# USB_to_UART_controller.net
KiCad netlist of a schematic drawn in Altium Designer
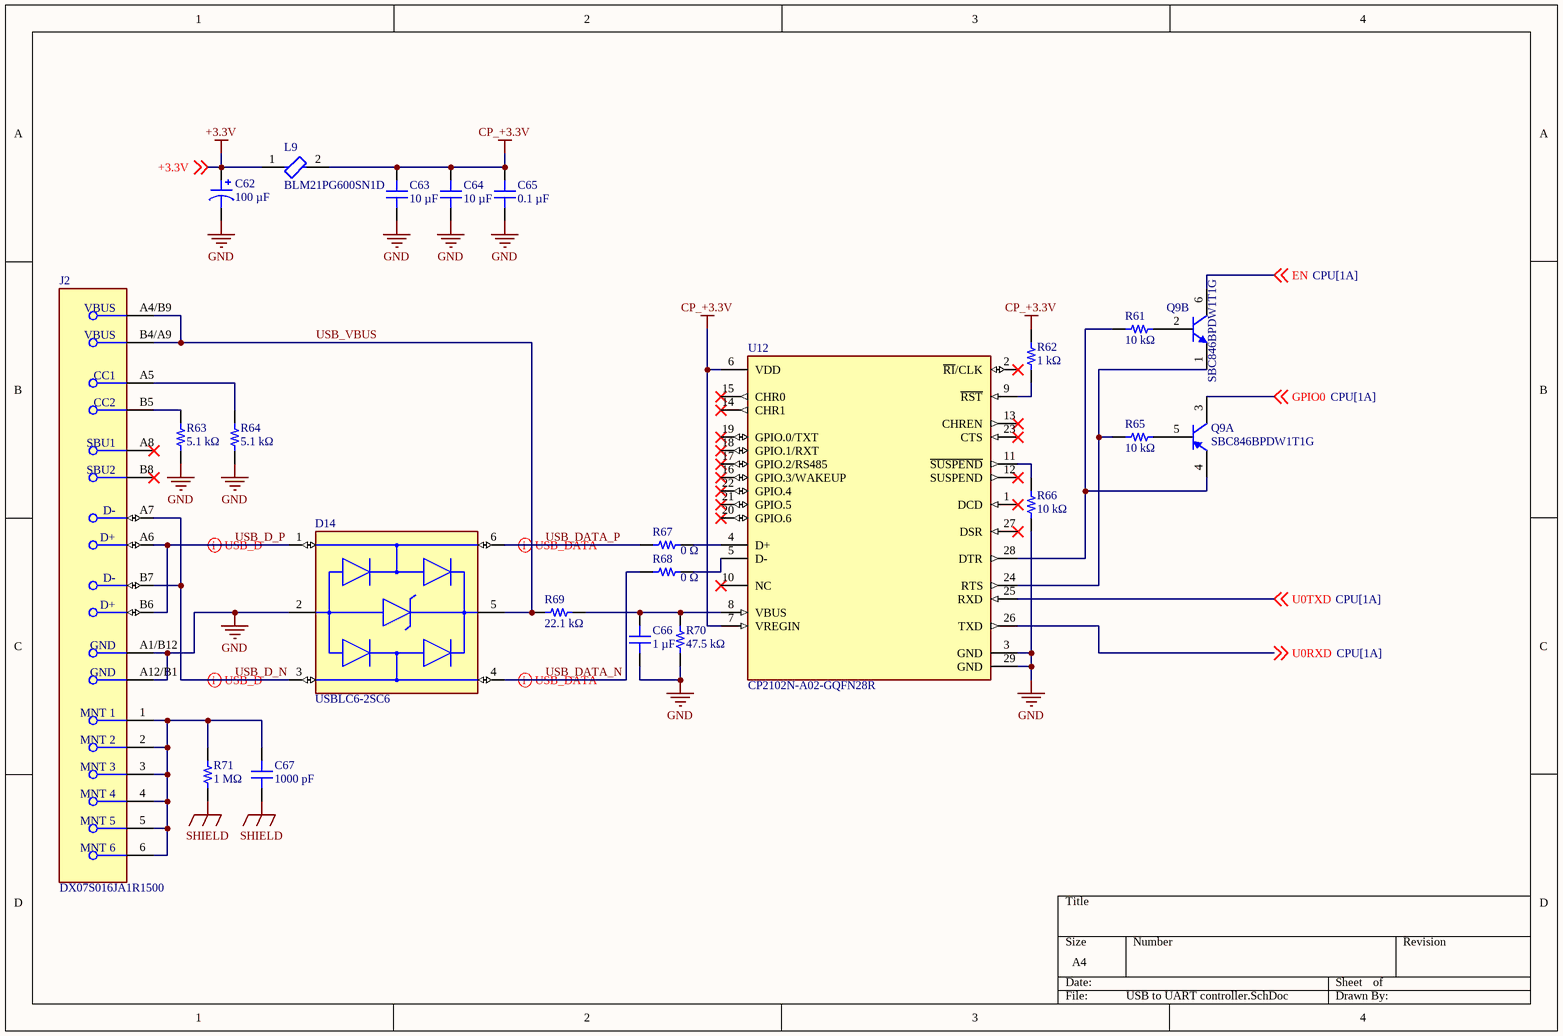
[diagram p0: USB to UART controller.SchDoc]

(export (version "E")
  (design (tool "Eeschema 10.0.6"))
  (components
    (comp (ref "C62")
      (value "100 µF")
      (footprint "CAP POL 1411_3528")
      (description "CAP TANT 100UF 20% 6.3V 1411")
      (fields (field (name "PART NUMBER") "T494B107M006AT") (field (name "MANUFACTURER") "KEMET"))
      (libsource (lib "Celestial Altium Library - altium_library") (part "Polarised Capacitor"))
    )
    (comp (ref "C63")
      (value "10 µF")
      (footprint "CAP 0805_2012")
      (description "CAP CER 10UF 6.3V X7R 0805")
      (fields
        (field (name "PART NUMBER") "CGA4J1X7R0J106K125AC")
        (field (name "CAPACITANCE") "10 µF")
        (field (name "MANUFACTURER") "TDK Corporation")
      )
      (libsource (lib "Celestial Altium Library - altium_library") (part "Capacitor"))
    )
    (comp (ref "C64")
      (value "10 µF")
      (footprint "CAP 0805_2012")
      (description "CAP CER 10UF 6.3V X7R 0805")
      (fields
        (field (name "PART NUMBER") "CGA4J1X7R0J106K125AC")
        (field (name "CAPACITANCE") "10 µF")
        (field (name "MANUFACTURER") "TDK Corporation")
      )
      (libsource (lib "Celestial Altium Library - altium_library") (part "Capacitor"))
    )
    (comp (ref "C65")
      (value "0.1 µF")
      (footprint "CAP 0603_1608")
      (description "CAP CER 0.1UF 50V X7R 0603")
      (fields
        (field (name "PART NUMBER") "C1608X7R1H104K080AE")
        (field (name "CAPACITANCE") "0.1 µF")
        (field (name "MANUFACTURER") "TDK Corporation")
      )
      (libsource (lib "Celestial Altium Library - altium_library") (part "Capacitor"))
    )
    (comp (ref "C66")
      (value "1 µF")
      (footprint "CAP 0805_2012")
      (description "CAP CER 1UF 25V X7R 0805")
      (fields
        (field (name "PART NUMBER") "C2012X7R1E105K125AB")
        (field (name "CAPACITANCE") "1 µF")
        (field (name "MANUFACTURER") "TDK Corporation")
      )
      (libsource (lib "Celestial Altium Library - altium_library") (part "Capacitor"))
    )
    (comp (ref "C67")
      (value "1000 pF")
      (footprint "CAP 1210_3225 - 1MM")
      (description "CAP CER 1000PF 2KV C0G/NP0 1210")
      (fields (field (name "PART NUMBER") "KGM32LCG3D102JU") (field (name "MANUFACTURER") "KYOCERA AVX"))
      (libsource (lib "Celestial Altium Library - altium_library") (part "Capacitor"))
    )
    (comp (ref "D14")
      (value "USBLC6-2SC6")
      (footprint "FP-SOT-666-MFG")
      (description "TVS DIODE 5.25V 17V SOT666")
      (fields (field (name "MANUFACTURER") "STMicroelectronics"))
      (libsource (lib "Altium Content Vault") (part "c871e55f7e3243d341edbd671b98d92"))
    )
    (comp (ref "J2")
      (value "DX07S016JA1R1500")
      (footprint "FP-DX07S016JA1R1500-MFG")
      (description "CONN RCP USB2.0 TYP C 24P SMD RA")
      (libsource (lib "Altium Content Vault") (part "7f3e9989102a0f22bff9cb010881d34"))
    )
    (comp (ref "L9")
      (value "BLM21PG600SN1D")
      (footprint "FP-BLM21-0_2-t0_85-e0_5-d-IPC_A")
      (description "Chip Ferrite Bead, 0805, 60Ω @ 100MHz, 0.02Ω, 25%, 3.5A")
      (fields (field (name "TOLERANCE") "25%"))
      (libsource (lib "Altium Content Vault") (part "5f30dd21d616792df468990f7003faa"))
    )
    (comp (ref "Q9")
      (value "SBC846BPDW1T1G")
      (footprint "ONSC-SOT-363-6-419B-02_V")
      (description "Dual General Purpose Transistors, NPN / PNP (Complementary), 6-Pin SOT-363, Pb-Free, Tape and Reel")
      (fields (field (name "MANUFACTURER") "On Semiconductor"))
      (libsource (lib "Altium Content Vault") (part "ONSC-NPN_PNP-6"))
    )
    (comp (ref "R61")
      (value "10 kΩ")
      (footprint "RES 0603_1608")
      (description "RES SMD 10K OHM 1% 1/10W 0603")
      (fields (field (name "PART NUMBER") "CRCW060310K0FKEA") (field (name "MANUFACTURER") "Vishay Dale"))
      (libsource (lib "Celestial Altium Library - altium_library") (part "Resistor"))
    )
    (comp (ref "R62")
      (value "1 kΩ")
      (footprint "RES 0603_1608")
      (description "RES SMD 1K OHM 1% 1/10W 0603")
      (fields (field (name "PART NUMBER") "CRCW06031K00FKEA") (field (name "MANUFACTURER") "Vishay Dale"))
      (libsource (lib "Celestial Altium Library - altium_library") (part "Resistor"))
    )
    (comp (ref "R63")
      (value "5.1 kΩ")
      (footprint "RES 0603_1608")
      (description "RES SMD 5.1K OHM 1% 1/10W 0603")
      (fields (field (name "PART NUMBER") "CRCW06035K10FKEA") (field (name "MANUFACTURER") "Vishay Dale"))
      (libsource (lib "Celestial Altium Library - altium_library") (part "Resistor"))
    )
    (comp (ref "R64")
      (value "5.1 kΩ")
      (footprint "RES 0603_1608")
      (description "RES SMD 5.1K OHM 1% 1/10W 0603")
      (fields (field (name "PART NUMBER") "CRCW06035K10FKEA") (field (name "MANUFACTURER") "Vishay Dale"))
      (libsource (lib "Celestial Altium Library - altium_library") (part "Resistor"))
    )
    (comp (ref "R65")
      (value "10 kΩ")
      (footprint "RES 0603_1608")
      (description "RES SMD 10K OHM 1% 1/10W 0603")
      (fields (field (name "PART NUMBER") "CRCW060310K0FKEA") (field (name "MANUFACTURER") "Vishay Dale"))
      (libsource (lib "Celestial Altium Library - altium_library") (part "Resistor"))
    )
    (comp (ref "R66")
      (value "10 kΩ")
      (footprint "RES 0603_1608")
      (description "RES SMD 10K OHM 1% 1/10W 0603")
      (fields (field (name "PART NUMBER") "CRCW060310K0FKEA") (field (name "MANUFACTURER") "Vishay Dale"))
      (libsource (lib "Celestial Altium Library - altium_library") (part "Resistor"))
    )
    (comp (ref "R67")
      (value "0 Ω")
      (footprint "RES 0603_1608")
      (description "RES SMD 0 OHM JUMPER 1/10W 0603")
      (fields
        (field (name "PART NUMBER") "ERJ-3GEY0R00V")
        (field (name "MANUFACTURER") "Panasonic Electronic Components")
      )
      (libsource (lib "Celestial Altium Library - altium_library") (part "Resistor"))
    )
    (comp (ref "R68")
      (value "0 Ω")
      (footprint "RES 0603_1608")
      (description "RES SMD 0 OHM JUMPER 1/10W 0603")
      (fields
        (field (name "PART NUMBER") "ERJ-3GEY0R00V")
        (field (name "MANUFACTURER") "Panasonic Electronic Components")
      )
      (libsource (lib "Celestial Altium Library - altium_library") (part "Resistor"))
    )
    (comp (ref "R69")
      (value "22.1 kΩ")
      (footprint "RES 0603_1608")
      (description "RES SMD 22.1K OHM 1% 1/10W 0603")
      (fields (field (name "PART NUMBER") "CRCW060322K1FKEA") (field (name "MANUFACTURER") "Vishay Dale"))
      (libsource (lib "Celestial Altium Library - altium_library") (part "Resistor"))
    )
    (comp (ref "R70")
      (value "47.5 kΩ")
      (footprint "RES 0603_1608")
      (description "RES SMD 47.5K OHM 1% 1/10W 0603")
      (fields (field (name "PART NUMBER") "CRCW060347K5FKEA") (field (name "MANUFACTURER") "Vishay Dale"))
      (libsource (lib "Celestial Altium Library - altium_library") (part "Resistor"))
    )
    (comp (ref "R71")
      (value "1 MΩ")
      (footprint "RES 0805_2012")
      (description "RES SMD 1M OHM 1% 1/2W 0805")
      (fields (field (name "PART NUMBER") "RCS08051M00FKEA") (field (name "MANUFACTURER") "Vishay Dale"))
      (libsource (lib "Celestial Altium Library - altium_library") (part "Resistor"))
    )
    (comp (ref "U12")
      (value "CP2102N-A02-GQFN28R")
      (footprint "FP-CP2102N-A02-GQFN28R-MFG")
      (description "IC USB TO UART BRIDGE QFN28")
      (libsource (lib "Altium Content Vault") (part "670edaef084fb69d2a747396d70a05e"))
    )
  )
  (nets
    (net (code "1") (name "+3.3V") (class "Default")
      (node (ref "C62") (pin "1") (pinfunction "1_1") (pintype "passive"))
      (node (ref "L9") (pin "1") (pinfunction "1_1") (pintype "passive"))
    )
    (net (code "2") (name "/USB_DATA_N") (class "Default")
      (node (ref "D14") (pin "4") (pinfunction "I/O2_4") (pintype "bidirectional"))
      (node (ref "R68") (pin "1") (pinfunction "1_1") (pintype "passive"))
    )
    (net (code "3") (name "/USB_DATA_P") (class "Default")
      (node (ref "D14") (pin "6") (pinfunction "I/O1_6") (pintype "bidirectional"))
      (node (ref "R67") (pin "1") (pinfunction "1_1") (pintype "passive"))
    )
    (net (code "4") (name "/USB_D_N") (class "Default")
      (node (ref "D14") (pin "3") (pinfunction "I/O2_3") (pintype "bidirectional"))
      (node (ref "J2") (pin "A7") (pinfunction "D-_A7") (pintype "bidirectional"))
      (node (ref "J2") (pin "B7") (pinfunction "D-_B7") (pintype "bidirectional"))
    )
    (net (code "5") (name "/USB_D_P") (class "Default")
      (node (ref "D14") (pin "1") (pinfunction "I/O1_1") (pintype "bidirectional"))
      (node (ref "J2") (pin "A6") (pinfunction "D+_A6") (pintype "bidirectional"))
      (node (ref "J2") (pin "B6") (pinfunction "D+_B6") (pintype "bidirectional"))
    )
    (net (code "6") (name "/USB_VBUS") (class "Default")
      (node (ref "D14") (pin "5") (pinfunction "VBUS_5") (pintype "power_in"))
      (node (ref "J2") (pin "A4/B9") (pinfunction "VBUS_A4/B9") (pintype "power_in"))
      (node (ref "J2") (pin "B4/A9") (pinfunction "VBUS_B4/A9") (pintype "power_in"))
      (node (ref "R69") (pin "2") (pinfunction "2_2") (pintype "passive"))
    )
    (net (code "7") (name "CP_+3.3V") (class "Default")
      (node (ref "C63") (pin "2") (pinfunction "2_2") (pintype "passive"))
      (node (ref "C64") (pin "2") (pinfunction "2_2") (pintype "passive"))
      (node (ref "C65") (pin "2") (pinfunction "2_2") (pintype "passive"))
      (node (ref "L9") (pin "2") (pinfunction "2_2") (pintype "passive"))
      (node (ref "R62") (pin "2") (pinfunction "2_2") (pintype "passive"))
      (node (ref "U12") (pin "6") (pinfunction "VDD_6") (pintype "power_in"))
      (node (ref "U12") (pin "7") (pinfunction "VREGIN_7") (pintype "input"))
    )
    (net (code "8") (name "EN") (class "Default")
      (node (ref "Q9") (pin "6") (pinfunction "C_6") (pintype "passive"))
    )
    (net (code "9") (name "GND") (class "Default")
      (node (ref "C62") (pin "2") (pinfunction "2_2") (pintype "passive"))
      (node (ref "C63") (pin "1") (pinfunction "1_1") (pintype "passive"))
      (node (ref "C64") (pin "1") (pinfunction "1_1") (pintype "passive"))
      (node (ref "C65") (pin "1") (pinfunction "1_1") (pintype "passive"))
      (node (ref "C66") (pin "1") (pinfunction "1_1") (pintype "passive"))
      (node (ref "D14") (pin "2") (pinfunction "GND_2") (pintype "power_in"))
      (node (ref "J2") (pin "A1/B12") (pinfunction "GND_A1/B12") (pintype "power_in"))
      (node (ref "J2") (pin "A12/B1") (pinfunction "GND_A12/B1") (pintype "power_in"))
      (node (ref "R63") (pin "1") (pinfunction "1_1") (pintype "passive"))
      (node (ref "R64") (pin "1") (pinfunction "1_1") (pintype "passive"))
      (node (ref "R66") (pin "1") (pinfunction "1_1") (pintype "passive"))
      (node (ref "R70") (pin "1") (pinfunction "1_1") (pintype "passive"))
      (node (ref "U12") (pin "29") (pinfunction "GND_29") (pintype "power_in"))
      (node (ref "U12") (pin "3") (pinfunction "GND_3") (pintype "power_in"))
    )
    (net (code "10") (name "GPIO0") (class "Default")
      (node (ref "Q9") (pin "3") (pinfunction "C_3") (pintype "passive"))
    )
    (net (code "11") (name "Net-(J2-CC1)") (class "Default")
      (node (ref "J2") (pin "A5") (pinfunction "CC1_A5") (pintype "passive"))
      (node (ref "R64") (pin "2") (pinfunction "2_2") (pintype "passive"))
    )
    (net (code "12") (name "Net-(J2-CC2)") (class "Default")
      (node (ref "J2") (pin "B5") (pinfunction "CC2_B5") (pintype "passive"))
      (node (ref "R63") (pin "2") (pinfunction "2_2") (pintype "passive"))
    )
    (net (code "13") (name "Net-(J2-MNT_1)") (class "Default")
      (node (ref "C67") (pin "2") (pinfunction "2_2") (pintype "passive"))
      (node (ref "J2") (pin "1") (pinfunction "MNT_1_1") (pintype "passive"))
      (node (ref "J2") (pin "2") (pinfunction "MNT_2_2") (pintype "passive"))
      (node (ref "J2") (pin "3") (pinfunction "MNT_3_3") (pintype "passive"))
      (node (ref "J2") (pin "4") (pinfunction "MNT_4_4") (pintype "passive"))
      (node (ref "J2") (pin "5") (pinfunction "MNT_5_5") (pintype "passive"))
      (node (ref "J2") (pin "6") (pinfunction "MNT_6_6") (pintype "passive"))
      (node (ref "R71") (pin "2") (pinfunction "2_2") (pintype "passive"))
    )
    (net (code "14") (name "Net-(Q9A-B)") (class "Default")
      (node (ref "Q9") (pin "5") (pinfunction "B_5") (pintype "passive"))
      (node (ref "R65") (pin "1") (pinfunction "1_1") (pintype "passive"))
    )
    (net (code "15") (name "Net-(Q9A-E)") (class "Default")
      (node (ref "Q9") (pin "4") (pinfunction "E_4") (pintype "passive"))
      (node (ref "R61") (pin "2") (pinfunction "2_2") (pintype "passive"))
      (node (ref "U12") (pin "28") (pinfunction "DTR_28") (pintype "output"))
    )
    (net (code "16") (name "Net-(Q9B-B)") (class "Default")
      (node (ref "Q9") (pin "2") (pinfunction "B_2") (pintype "passive"))
      (node (ref "R61") (pin "1") (pinfunction "1_1") (pintype "passive"))
    )
    (net (code "17") (name "Net-(Q9B-E)") (class "Default")
      (node (ref "Q9") (pin "1") (pinfunction "E_1") (pintype "passive"))
      (node (ref "R65") (pin "2") (pinfunction "2_2") (pintype "passive"))
      (node (ref "U12") (pin "24") (pinfunction "RTS_24") (pintype "output"))
    )
    (net (code "18") (name "Net-(U12-D+)") (class "Default")
      (node (ref "R67") (pin "2") (pinfunction "2_2") (pintype "passive"))
      (node (ref "U12") (pin "4") (pinfunction "D+_4") (pintype "passive"))
    )
    (net (code "19") (name "Net-(U12-D-)") (class "Default")
      (node (ref "R68") (pin "2") (pinfunction "2_2") (pintype "passive"))
      (node (ref "U12") (pin "5") (pinfunction "D-_5") (pintype "passive"))
    )
    (net (code "20") (name "Net-(U12-VBUS)") (class "Default")
      (node (ref "C66") (pin "2") (pinfunction "2_2") (pintype "passive"))
      (node (ref "R69") (pin "1") (pinfunction "1_1") (pintype "passive"))
      (node (ref "R70") (pin "2") (pinfunction "2_2") (pintype "passive"))
      (node (ref "U12") (pin "8") (pinfunction "VBUS_8") (pintype "input"))
    )
    (net (code "21") (name "Net-(U12-~{RST})") (class "Default")
      (node (ref "R62") (pin "1") (pinfunction "1_1") (pintype "passive"))
      (node (ref "U12") (pin "9") (pinfunction "~{RST}_9") (pintype "input"))
    )
    (net (code "22") (name "Net-(U12-~{SUSPEND})") (class "Default")
      (node (ref "R66") (pin "2") (pinfunction "2_2") (pintype "passive"))
      (node (ref "U12") (pin "11") (pinfunction "~{SUSPEND}_11") (pintype "output"))
    )
    (net (code "23") (name "SHIELD") (class "Default")
      (node (ref "C67") (pin "1") (pinfunction "1_1") (pintype "passive"))
      (node (ref "R71") (pin "1") (pinfunction "1_1") (pintype "passive"))
    )
    (net (code "24") (name "U0RXD") (class "Default")
      (node (ref "U12") (pin "26") (pinfunction "TXD_26") (pintype "output"))
    )
    (net (code "25") (name "U0TXD") (class "Default")
      (node (ref "U12") (pin "25") (pinfunction "RXD_25") (pintype "input"))
    )
    (net (code "26") (name "unconnected-(J2-SBU1-PadA8)") (class "Default")
      (node (ref "J2") (pin "A8") (pinfunction "SBU1_A8") (pintype "passive+no_connect"))
    )
    (net (code "27") (name "unconnected-(J2-SBU2-PadB8)") (class "Default")
      (node (ref "J2") (pin "B8") (pinfunction "SBU2_B8") (pintype "passive+no_connect"))
    )
    (net (code "28") (name "unconnected-(U12-CHR0-Pad15)") (class "Default")
      (node (ref "U12") (pin "15") (pinfunction "CHR0_15") (pintype "output+no_connect"))
    )
    (net (code "29") (name "unconnected-(U12-CHR1-Pad14)") (class "Default")
      (node (ref "U12") (pin "14") (pinfunction "CHR1_14") (pintype "output+no_connect"))
    )
    (net (code "30") (name "unconnected-(U12-CHREN-Pad13)") (class "Default")
      (node (ref "U12") (pin "13") (pinfunction "CHREN_13") (pintype "output+no_connect"))
    )
    (net (code "31") (name "unconnected-(U12-CTS-Pad23)") (class "Default")
      (node (ref "U12") (pin "23") (pinfunction "CTS_23") (pintype "input+no_connect"))
    )
    (net (code "32") (name "unconnected-(U12-DCD-Pad1)") (class "Default")
      (node (ref "U12") (pin "1") (pinfunction "DCD_1") (pintype "input+no_connect"))
    )
    (net (code "33") (name "unconnected-(U12-DSR-Pad27)") (class "Default")
      (node (ref "U12") (pin "27") (pinfunction "DSR_27") (pintype "input+no_connect"))
    )
    (net (code "34") (name "unconnected-(U12-GPIO.0{slash}TXT-Pad19)") (class "Default")
      (node (ref "U12") (pin "19") (pinfunction "GPIO.0/TXT_19") (pintype "bidirectional+no_connect"))
    )
    (net (code "35") (name "unconnected-(U12-GPIO.1{slash}RXT-Pad18)") (class "Default")
      (node (ref "U12") (pin "18") (pinfunction "GPIO.1/RXT_18") (pintype "bidirectional+no_connect"))
    )
    (net (code "36") (name "unconnected-(U12-GPIO.2{slash}RS485-Pad17)") (class "Default")
      (node (ref "U12") (pin "17") (pinfunction "GPIO.2/RS485_17") (pintype "bidirectional+no_connect"))
    )
    (net (code "37") (name "unconnected-(U12-GPIO.3{slash}WAKEUP-Pad16)") (class "Default")
      (node (ref "U12") (pin "16") (pinfunction "GPIO.3/WAKEUP_16") (pintype "bidirectional+no_connect"))
    )
    (net (code "38") (name "unconnected-(U12-GPIO.4-Pad22)") (class "Default")
      (node (ref "U12") (pin "22") (pinfunction "GPIO.4_22") (pintype "bidirectional+no_connect"))
    )
    (net (code "39") (name "unconnected-(U12-GPIO.5-Pad21)") (class "Default")
      (node (ref "U12") (pin "21") (pinfunction "GPIO.5_21") (pintype "bidirectional+no_connect"))
    )
    (net (code "40") (name "unconnected-(U12-GPIO.6-Pad20)") (class "Default")
      (node (ref "U12") (pin "20") (pinfunction "GPIO.6_20") (pintype "bidirectional+no_connect"))
    )
    (net (code "41") (name "unconnected-(U12-NC-Pad10)") (class "Default")
      (node (ref "U12") (pin "10") (pinfunction "NC_10") (pintype "passive+no_connect"))
    )
    (net (code "42") (name "unconnected-(U12-SUSPEND-Pad12)") (class "Default")
      (node (ref "U12") (pin "12") (pinfunction "SUSPEND_12") (pintype "output+no_connect"))
    )
    (net (code "43") (name "unconnected-(U12-~{RI}{slash}CLK-Pad2)") (class "Default")
      (node (ref "U12") (pin "2") (pinfunction "~{RI}/CLK_2") (pintype "bidirectional+no_connect"))
    )
  )
)
